# Power_Supply.net
KiCad netlist of a schematic drawn in Altium Designer
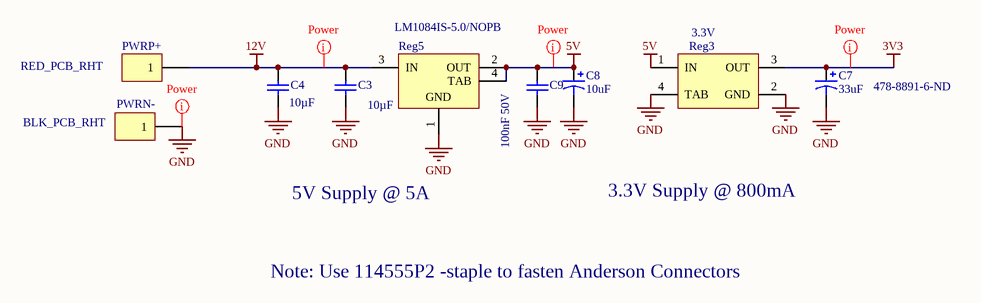
[diagram p0: Power Supply.SchDoc]

(export (version "E")
  (design (tool "Eeschema 10.0.6"))
  (components
    (comp (ref "C3")
      (value "10µF")
      (footprint "CAPC2013X135X45ML10T25")
      (fields
        (field (name "PART NUMBER") "GRM21BR61E106KA73L")
        (field (name "MANUFACTURER") "Murata")
        (field (name "TOLERANCE") "±10%")
      )
      (libsource (lib "Altium Content Vault") (part "CMP-2007-03541-1"))
    )
    (comp (ref "C4")
      (value "10µF")
      (footprint "CAPC2013X135X45ML10T25")
      (fields
        (field (name "PART NUMBER") "GRM21BR61E106KA73L")
        (field (name "MANUFACTURER") "Murata")
        (field (name "TOLERANCE") "±10%")
      )
      (libsource (lib "Altium Content Vault") (part "CMP-2007-03541-1"))
    )
    (comp (ref "C7")
      (value "33uF")
      (footprint "AVX-CAPC3528_V")
      (description "Capacitor, Tantalum, 10uF 10% 20V MCCT-B (3528)")
      (fields
        (field (name "SUPPLIER PART NUMBER 1") "478-8891-6-ND")
        (field (name "MANUFACTURER") "Kyocera / AVX")
        (field (name "MANUFACTURER PART NUMBER") "TAJB336K006RNJ")
      )
      (libsource (lib "Altium Content Vault") (part "CMP-0279-00001-1"))
    )
    (comp (ref "C8")
      (value "10uF")
      (footprint "AVX-CAPC3528_V")
      (description "Capacitor, Tantalum, 10uF 10% 20V MCCT-B (3528)")
      (fields (field (name "PARTNUMBER") "TAJB106K020R") (field (name "MANUFACTURER") "AVX"))
      (libsource (lib "Altium Content Vault") (part "CMP-0279-00001-1"))
    )
    (comp (ref "C9")
      (value "100nF 50V")
      (footprint "0603C_L")
      (fields
        (field (name "MANUFACTURER") "Yageo")
        (field (name "MANUFACTURER PART NUMBER") "CC0603ZRY5V9BB104")
        (field (name "TOLERANCE") "-20%, +80%")
      )
      (libsource (lib "PoleV2PaintV5") (part "Cap100nF_50V_0603"))
    )
    (comp (ref "PWRN-")
      (value "BLK_PCB_RHT")
      (footprint "Anderson_BLK_RHT_BOT")
      (description "1 pin Anderson")
      (fields
        (field (name "MANUFACTURER") "Anderson Power Products (APP)")
        (field (name "MANUFACTURER PART NUMBER") "1377G1, 1377G2, 1327-BK,137G6-BK")
      )
      (libsource (lib "WCT") (part "Anderson-1Pin BLK_PCB_RHT"))
    )
    (comp (ref "PWRP+")
      (value "RED_PCB_RHT")
      (footprint "Anderson_Red_RHT_BOT")
      (description "1 pin Anderson")
      (fields
        (field (name "MANUFACTURER") "Anderson Power Products (APP)")
        (field (name "MANUFACTURER PART NUMBER") "1377G1, 1377G2, 1327-BK,137G6-BK")
      )
      (libsource (lib "WCT") (part "Anderson-1Pin RED_PCB_RHT"))
    )
    (comp (ref "Reg3")
      (value "3.3V")
      (footprint "DCY0004A_M")
      (description "1A Low Dropout Regulator for 5V to 3.3V Conversion, 4-pin SOT-223, Pb-Free")
      (fields
        (field (name "MANUFACTURER") "Texas Instruments")
        (field (name "MANUFACTURER PART NUMBER") "LM3940IMP-3.3/NOPB")
      )
      (libsource (lib "Altium Content Vault") (part "CMP-0062-01788-3"))
    )
    (comp (ref "Reg5")
      (value "LM1084IS-5.0/NOPB")
      (footprint "KTT0003B_L")
      (description "5A Low Dropout Positive Regulators, 3-pin TO-263, Pb-Free")
      (fields (field (name "MANUFACTURER") "Texas Instruments"))
      (libsource (lib "Altium Content Vault") (part "CMP-0062-00575-4"))
    )
  )
  (nets
    (net (code "1") (name "3V3") (class "Default")
      (node (ref "C7") (pin "1") (pinfunction "1_1") (pintype "passive"))
      (node (ref "Reg3") (pin "3") (pinfunction "OUT_3") (pintype "power_in"))
    )
    (net (code "2") (name "5V") (class "Default")
      (node (ref "C8") (pin "1") (pinfunction "1_1") (pintype "passive"))
      (node (ref "C9") (pin "2") (pinfunction "2_2") (pintype "passive"))
      (node (ref "Reg3") (pin "1") (pinfunction "IN_1") (pintype "power_in"))
      (node (ref "Reg5") (pin "2") (pinfunction "OUT_2") (pintype "power_in"))
      (node (ref "Reg5") (pin "4") (pinfunction "TAB_4") (pintype "power_in"))
    )
    (net (code "3") (name "12V") (class "Default")
      (node (ref "C3") (pin "2") (pinfunction "2_2") (pintype "passive"))
      (node (ref "C4") (pin "2") (pinfunction "2_2") (pintype "passive"))
      (node (ref "PWRP+") (pin "1") (pinfunction "1_1") (pintype "passive"))
      (node (ref "Reg5") (pin "3") (pinfunction "IN_3") (pintype "power_in"))
    )
    (net (code "4") (name "GND") (class "Default")
      (node (ref "C3") (pin "1") (pinfunction "1_1") (pintype "passive"))
      (node (ref "C4") (pin "1") (pinfunction "1_1") (pintype "passive"))
      (node (ref "C7") (pin "2") (pinfunction "2_2") (pintype "passive"))
      (node (ref "C8") (pin "2") (pinfunction "2_2") (pintype "passive"))
      (node (ref "C9") (pin "1") (pinfunction "1_1") (pintype "passive"))
      (node (ref "PWRN-") (pin "1") (pinfunction "1_1") (pintype "passive"))
      (node (ref "Reg3") (pin "2") (pinfunction "GND_2") (pintype "power_in"))
      (node (ref "Reg3") (pin "4") (pinfunction "TAB_4") (pintype "power_in"))
      (node (ref "Reg5") (pin "1") (pinfunction "GND_1") (pintype "power_in"))
    )
  )
)
